# cj-buttons.net
KiCad netlist of a schematic drawn in EAGLE
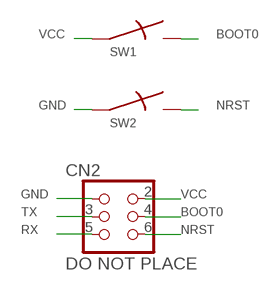
[diagram p0: schematic, sheet 1]

(export (version "E")
  (design (tool "Eeschema 10.0.6"))
  (components
    (comp (ref "CN2")
      (value "DO NOT PLACE")
      (footprint "eagle-import:HEADER-3X2-PTH1.27")
      (libsource (lib "eagle-import") (part "HEADER-3X2-PTH1.27"))
    )
    (comp (ref "SW1")
      (value "SWITCHKMR211")
      (footprint "eagle-import:KMR211")
      (libsource (lib "eagle-import") (part "SWITCHKMR211"))
    )
    (comp (ref "SW2")
      (value "SWITCHKMR211")
      (footprint "eagle-import:KMR211")
      (libsource (lib "eagle-import") (part "SWITCHKMR211"))
    )
  )
  (nets
    (net (code "1") (name "/BOOT0") (class "Default")
      (node (ref "CN2") (pin "4") (pinfunction "P$4_4") (pintype "passive"))
      (node (ref "SW1") (pin "2") (pinfunction "P$2_2") (pintype "passive"))
      (node (ref "SW1") (pin "4") (pinfunction "P$2_4") (pintype "passive"))
    )
    (net (code "2") (name "/GND") (class "Default")
      (node (ref "CN2") (pin "1") (pinfunction "P$1_1") (pintype "passive"))
      (node (ref "SW2") (pin "1") (pinfunction "P$1_1") (pintype "passive"))
      (node (ref "SW2") (pin "3") (pinfunction "P$1_3") (pintype "passive"))
    )
    (net (code "3") (name "/NRST") (class "Default")
      (node (ref "CN2") (pin "6") (pinfunction "P$6_6") (pintype "passive"))
      (node (ref "SW2") (pin "2") (pinfunction "P$2_2") (pintype "passive"))
      (node (ref "SW2") (pin "4") (pinfunction "P$2_4") (pintype "passive"))
    )
    (net (code "4") (name "/RX") (class "Default")
      (node (ref "CN2") (pin "5") (pinfunction "P$5_5") (pintype "passive"))
    )
    (net (code "5") (name "/TX") (class "Default")
      (node (ref "CN2") (pin "3") (pinfunction "P$3_3") (pintype "passive"))
    )
    (net (code "6") (name "/VCC") (class "Default")
      (node (ref "CN2") (pin "2") (pinfunction "P$2_2") (pintype "passive"))
      (node (ref "SW1") (pin "1") (pinfunction "P$1_1") (pintype "passive"))
      (node (ref "SW1") (pin "3") (pinfunction "P$1_3") (pintype "passive"))
    )
  )
)
